# legatus_1_0.net
KiCad netlist of a schematic drawn in EAGLE
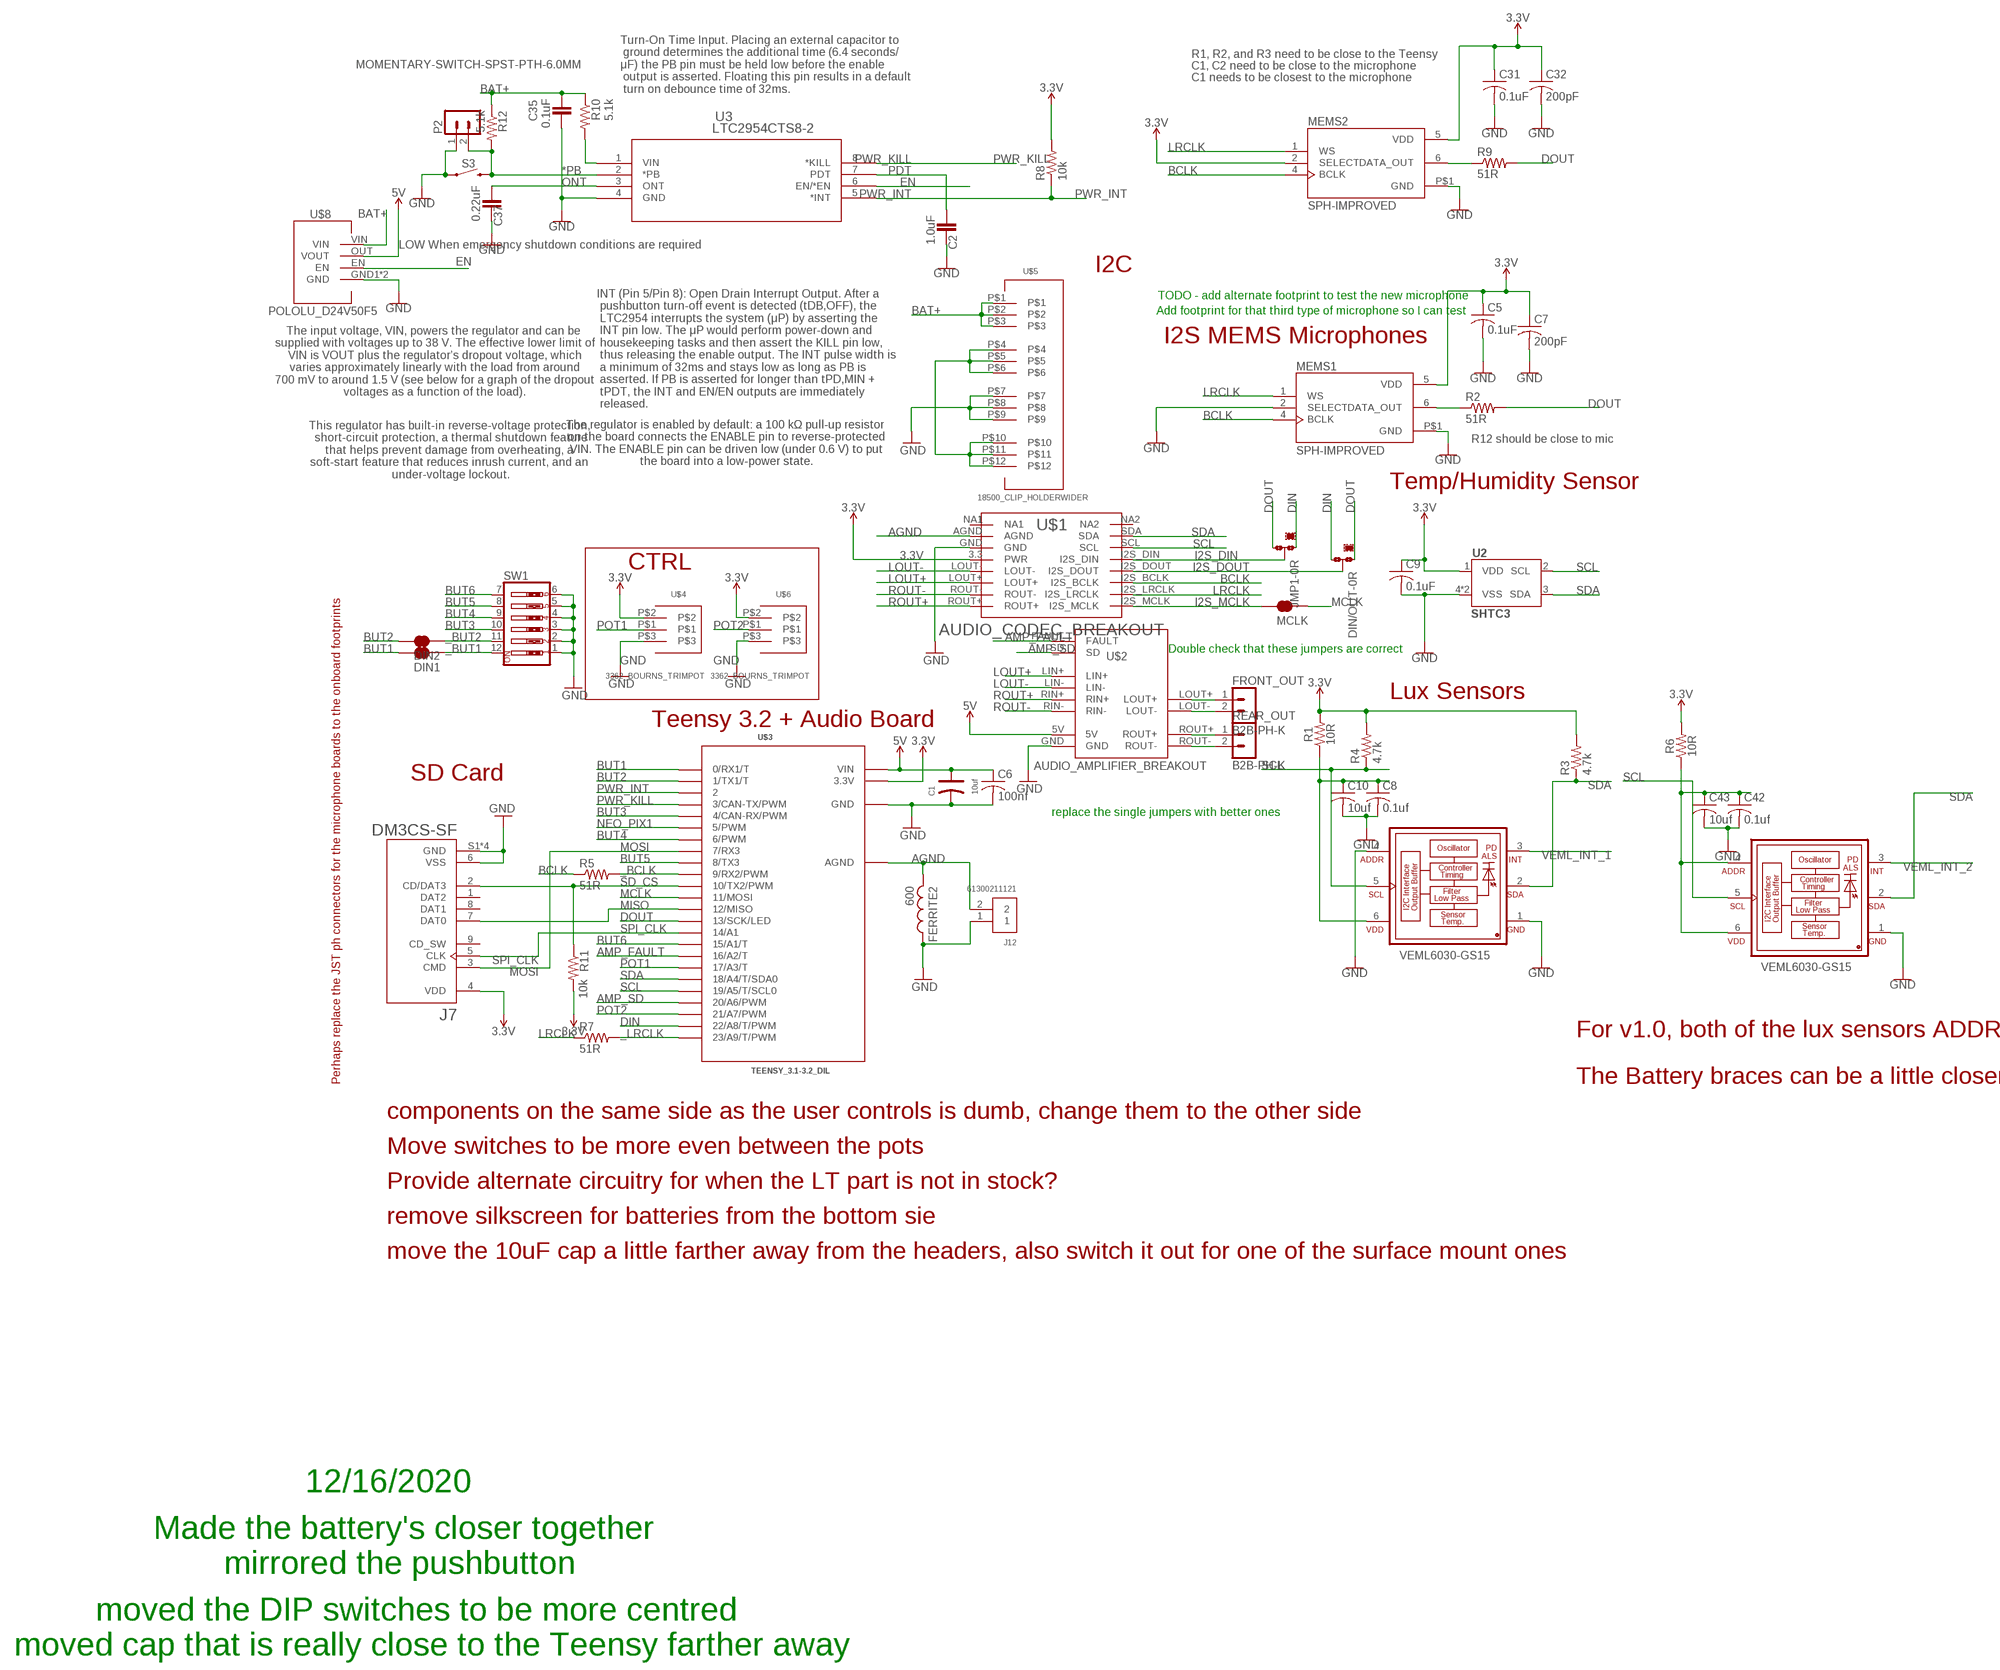
[diagram p0: schematic, sheet 1, part 1 of 2]
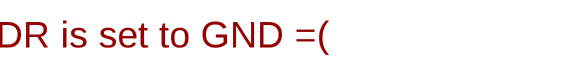
[diagram p1: schematic, sheet 1, part 2 of 2]
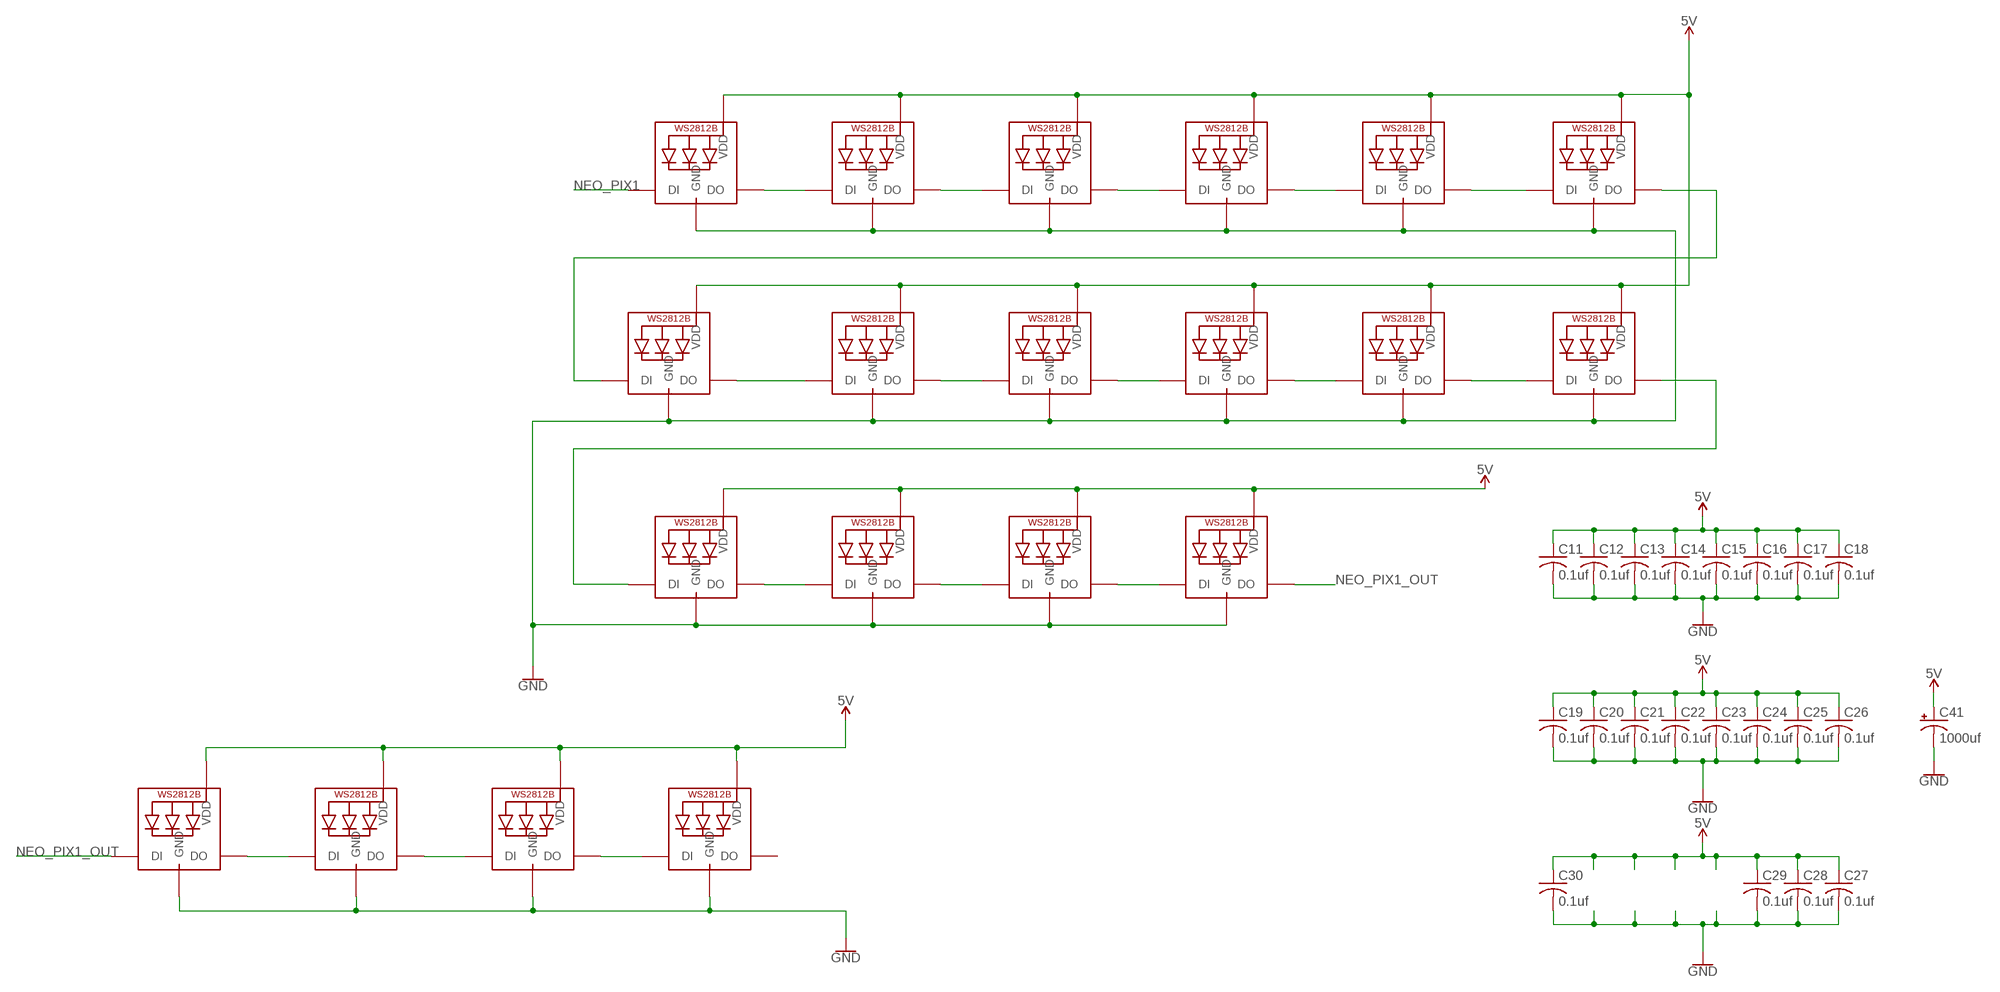
[diagram p2: schematic, sheet 2]

(export (version "E")
  (design (tool "Eeschema 10.0.6"))
  (components
    (comp (ref "C1")
      (value "10uf")
      (footprint "eagle-import:PC-D5.3MM")
      (fields (field (name "MPN") "KS 100uF/16V"))
      (libsource (lib "eagle-import") (part "DIP-ALUMINUM-47UF-16V(D5-H7MM)"))
    )
    (comp (ref "C2")
      (value "1.0uF")
      (footprint "eagle-import:CAPC2012X110")
      (libsource (lib "eagle-import") (part "CCHIP-0805(2012-METRIC)_"))
    )
    (comp (ref "C5")
      (value "0.1uF")
      (footprint "eagle-import:C0805")
      (libsource (lib "eagle-import") (part "rcl_334_C-USC0805"))
    )
    (comp (ref "C6")
      (value "100nf")
      (footprint "eagle-import:C2012")
      (libsource (lib "eagle-import") (part "C-USC2012"))
    )
    (comp (ref "C7")
      (value "200pF")
      (footprint "eagle-import:C0805")
      (libsource (lib "eagle-import") (part "rcl_334_C-USC0805"))
    )
    (comp (ref "C8")
      (value "0.1uf")
      (footprint "eagle-import:C0805")
      (libsource (lib "eagle-import") (part "rcl_334_C-USC0805"))
    )
    (comp (ref "C9")
      (value "0.1uF")
      (footprint "eagle-import:C0805")
      (libsource (lib "eagle-import") (part "rcl_334_C-USC0805"))
    )
    (comp (ref "C10")
      (value "10uf")
      (footprint "eagle-import:C0805")
      (libsource (lib "eagle-import") (part "rcl_334_C-USC0805"))
    )
    (comp (ref "C31")
      (value "0.1uF")
      (footprint "eagle-import:C0805")
      (libsource (lib "eagle-import") (part "rcl_334_C-USC0805"))
    )
    (comp (ref "C32")
      (value "200pF")
      (footprint "eagle-import:C0805")
      (libsource (lib "eagle-import") (part "rcl_334_C-USC0805"))
    )
    (comp (ref "C35")
      (value "0.1uF")
      (footprint "eagle-import:CAPC2012X110")
      (libsource (lib "eagle-import") (part "CCHIP-0805(2012-METRIC)_"))
    )
    (comp (ref "C37")
      (value "0.22uF")
      (footprint "eagle-import:CAPC2012X110")
      (libsource (lib "eagle-import") (part "CCHIP-0805(2012-METRIC)_"))
    )
    (comp (ref "C42")
      (value "0.1uf")
      (footprint "eagle-import:C0805")
      (libsource (lib "eagle-import") (part "rcl_334_C-USC0805"))
    )
    (comp (ref "C43")
      (value "10uf")
      (footprint "eagle-import:C0805")
      (libsource (lib "eagle-import") (part "rcl_334_C-USC0805"))
    )
    (comp (ref "DIN/OUT")
      (value "0R-JUMPB")
      (footprint "eagle-import:B0R-JMP")
      (libsource (lib "eagle-import") (part "0R-JUMPB"))
    )
    (comp (ref "DIN1")
      (value "JUMPER-SMT_2_NC_TRACE_SILK")
      (footprint "eagle-import:SMT-JUMPER_2_NC_TRACE_SILK")
      (libsource (lib "eagle-import") (part "JUMPER-SMT_2_NC_TRACE_SILK"))
    )
    (comp (ref "DIN2")
      (value "JUMPER-SMT_2_NC_TRACE_SILK")
      (footprint "eagle-import:SMT-JUMPER_2_NC_TRACE_SILK")
      (libsource (lib "eagle-import") (part "JUMPER-SMT_2_NC_TRACE_SILK"))
    )
    (comp (ref "FERRITE2")
      (value "600")
      (footprint "eagle-import:RESC0805_N")
      (libsource (lib "eagle-import") (part "INDUCTOR_0805_N"))
    )
    (comp (ref "FRONT_OUT")
      (value "B2B-PH-K")
      (footprint "eagle-import:B2B-PH-K")
      (libsource (lib "eagle-import") (part "B2B-PH-K"))
    )
    (comp (ref "J7")
      (value "DM3CS-SF")
      (footprint "eagle-import:HRS_DM3CS-SF")
      (fields (field (name "MF") "Hirose"))
      (libsource (lib "eagle-import") (part "DM3CS-SF"))
    )
    (comp (ref "J12")
      (value "61300211121")
      (footprint "eagle-import:61300211121")
      (fields
        (field (name "DIGI_KEY_PART_NUMBER") "732-5315-ND")
        (field (name "MANUFACTURER") "Wurth Electronics Inc.")
        (field (name "CREATED_BY") "PCBLayout.com")
      )
      (libsource (lib "eagle-import") (part "61300211121"))
    )
    (comp (ref "JMP1")
      (value "0R-JUMPB")
      (footprint "eagle-import:B0R-JMP")
      (libsource (lib "eagle-import") (part "0R-JUMPB"))
    )
    (comp (ref "MCLK")
      (value "JUMPER-SMT_2_NC_TRACE_SILK")
      (footprint "eagle-import:SMT-JUMPER_2_NC_TRACE_SILK")
      (libsource (lib "eagle-import") (part "JUMPER-SMT_2_NC_TRACE_SILK"))
    )
    (comp (ref "MEMS1")
      (value "SPH-IMPROVED")
      (footprint "eagle-import:MIC_SPH0645LM4H-B_LARGER_RING")
      (libsource (lib "eagle-import") (part "SPH-IMPROVED"))
    )
    (comp (ref "MEMS2")
      (value "SPH-IMPROVED")
      (footprint "eagle-import:MIC_SPH0645LM4H-B_LARGER_RING")
      (libsource (lib "eagle-import") (part "SPH-IMPROVED"))
    )
    (comp (ref "P2")
      (value "B2B-PH-K")
      (footprint "eagle-import:B2B-PH-K")
      (libsource (lib "eagle-import") (part "B2B-PH-K"))
    )
    (comp (ref "R1")
      (value "10R")
      (footprint "eagle-import:R0805")
      (libsource (lib "eagle-import") (part "audio amplifier example_970892_R-US_R0805"))
    )
    (comp (ref "R2")
      (value "51R")
      (footprint "eagle-import:M0805")
      (libsource (lib "eagle-import") (part "adafruit_420_R-US_M0805"))
    )
    (comp (ref "R3")
      (value "4.7k")
      (footprint "eagle-import:M0805")
      (libsource (lib "eagle-import") (part "adafruit_420_R-US_M0805"))
    )
    (comp (ref "R4")
      (value "4.7k")
      (footprint "eagle-import:M0805")
      (libsource (lib "eagle-import") (part "adafruit_420_R-US_M0805"))
    )
    (comp (ref "R5")
      (value "51R")
      (footprint "eagle-import:M0805")
      (libsource (lib "eagle-import") (part "adafruit_420_R-US_M0805"))
    )
    (comp (ref "R6")
      (value "10R")
      (footprint "eagle-import:R0805")
      (libsource (lib "eagle-import") (part "audio amplifier example_970892_R-US_R0805"))
    )
    (comp (ref "R7")
      (value "51R")
      (footprint "eagle-import:M0805")
      (libsource (lib "eagle-import") (part "adafruit_420_R-US_M0805"))
    )
    (comp (ref "R8")
      (value "10k")
      (footprint "eagle-import:R0805")
      (libsource (lib "eagle-import") (part "R-US_R0805"))
    )
    (comp (ref "R9")
      (value "51R")
      (footprint "eagle-import:M0805")
      (libsource (lib "eagle-import") (part "adafruit_420_R-US_M0805"))
    )
    (comp (ref "R10")
      (value "5.1k")
      (footprint "eagle-import:R0805")
      (libsource (lib "eagle-import") (part "R-US_R0805"))
    )
    (comp (ref "R11")
      (value "10k")
      (footprint "eagle-import:M0805")
      (libsource (lib "eagle-import") (part "rcl_R-US_M0805"))
    )
    (comp (ref "R12")
      (value "5.1k")
      (footprint "eagle-import:R0805")
      (libsource (lib "eagle-import") (part "R-US_R0805"))
    )
    (comp (ref "REAR_OUT")
      (value "B2B-PH-K")
      (footprint "eagle-import:B2B-PH-K")
      (libsource (lib "eagle-import") (part "B2B-PH-K"))
    )
    (comp (ref "S3")
      (value "MOMENTARY-SWITCH-SPST-PTH-6.0MM")
      (footprint "eagle-import:TACTILE_SWITCH_PTH_6.0MM")
      (libsource (lib "eagle-import") (part "MOMENTARY-SWITCH-SPST-PTH-6.0MM"))
    )
    (comp (ref "SW1")
      (value "SW_DIP-6")
      (footprint "eagle-import:EDG-06")
      (libsource (lib "eagle-import") (part "SW_DIP-6"))
    )
    (comp (ref "U$1")
      (value "AUDIO_CODEC_BREAKOUT")
      (footprint "eagle-import:HSS_CODEC_BREAKOUT")
      (libsource (lib "eagle-import") (part "AUDIO_CODEC_BREAKOUT"))
    )
    (comp (ref "U$2")
      (value "AUDIO_AMPLIFIER_BREAKOUT")
      (footprint "eagle-import:AUDIO_AMPLIFIER_BREAKOUT")
      (libsource (lib "eagle-import") (part "AUDIO_AMPLIFIER_BREAKOUT"))
    )
    (comp (ref "U$3")
      (value "TEENSY_3.1-3.2_DIL")
      (footprint "eagle-import:TEENSY_3.0-3.2&LC_DIL")
      (libsource (lib "eagle-import") (part "TEENSY_3.1-3.2_DIL"))
    )
    (comp (ref "U$4")
      (value "3362_BOURNS_TRIMPOT")
      (footprint "eagle-import:3362_BOURNS_TRIMPOT")
      (libsource (lib "eagle-import") (part "3362_BOURNS_TRIMPOT"))
    )
    (comp (ref "U$5")
      (value "18500_CLIP_HOLDERWIDER")
      (footprint "eagle-import:3PINBATTERY_CLIP_WIDER")
      (libsource (lib "eagle-import") (part "18500_CLIP_HOLDERWIDER"))
    )
    (comp (ref "U$6")
      (value "3362_BOURNS_TRIMPOT")
      (footprint "eagle-import:3362_BOURNS_TRIMPOT")
      (libsource (lib "eagle-import") (part "3362_BOURNS_TRIMPOT"))
    )
    (comp (ref "U$8")
      (value "POLOLU_D24V50F5")
      (footprint "eagle-import:POLOLU_D24V50F5")
      (libsource (lib "eagle-import") (part "POLOLU_D24V50F5"))
    )
    (comp (ref "U2")
      (value "SHTC3")
      (footprint "eagle-import:SHTC3")
      (libsource (lib "eagle-import") (part "SHTC3"))
    )
    (comp (ref "U3")
      (value "LTC2954CTS8-2")
      (footprint "eagle-import:TSOT-23_TS8")
      (fields (field (name "MF") "Analog Devices / Linear Technology"))
      (libsource (lib "eagle-import") (part "LTC2954CTS8-2"))
    )
    (comp (ref "VMEL1")
      (value "VEML6030-GS15")
      (footprint "eagle-import:VISHAY_VEML6030_2X2X0.87")
      (fields (field (name "MF") "Vishay Semiconductor"))
      (libsource (lib "eagle-import") (part "VEML6030-GS15"))
    )
    (comp (ref "VMEL2")
      (value "VEML6030-GS15")
      (footprint "eagle-import:VISHAY_VEML6030_2X2X0.87")
      (fields (field (name "MF") "Vishay Semiconductor"))
      (libsource (lib "eagle-import") (part "VEML6030-GS15"))
    )
    (comp (ref "C11")
      (value "0.1uf")
      (footprint "eagle-import:C0805")
      (libsource (lib "eagle-import") (part "rcl_334_C-USC0805"))
    )
    (comp (ref "C12")
      (value "0.1uf")
      (footprint "eagle-import:C0805")
      (libsource (lib "eagle-import") (part "rcl_334_C-USC0805"))
    )
    (comp (ref "C13")
      (value "0.1uf")
      (footprint "eagle-import:C0805")
      (libsource (lib "eagle-import") (part "rcl_334_C-USC0805"))
    )
    (comp (ref "C14")
      (value "0.1uf")
      (footprint "eagle-import:C0805")
      (libsource (lib "eagle-import") (part "rcl_334_C-USC0805"))
    )
    (comp (ref "C15")
      (value "0.1uf")
      (footprint "eagle-import:C0805")
      (libsource (lib "eagle-import") (part "rcl_334_C-USC0805"))
    )
    (comp (ref "C16")
      (value "0.1uf")
      (footprint "eagle-import:C0805")
      (libsource (lib "eagle-import") (part "rcl_334_C-USC0805"))
    )
    (comp (ref "C17")
      (value "0.1uf")
      (footprint "eagle-import:C0805")
      (libsource (lib "eagle-import") (part "rcl_334_C-USC0805"))
    )
    (comp (ref "C18")
      (value "0.1uf")
      (footprint "eagle-import:C0805")
      (libsource (lib "eagle-import") (part "rcl_334_C-USC0805"))
    )
    (comp (ref "C19")
      (value "0.1uf")
      (footprint "eagle-import:C0805")
      (libsource (lib "eagle-import") (part "rcl_334_C-USC0805"))
    )
    (comp (ref "C20")
      (value "0.1uf")
      (footprint "eagle-import:C0805")
      (libsource (lib "eagle-import") (part "rcl_334_C-USC0805"))
    )
    (comp (ref "C21")
      (value "0.1uf")
      (footprint "eagle-import:C0805")
      (libsource (lib "eagle-import") (part "rcl_334_C-USC0805"))
    )
    (comp (ref "C22")
      (value "0.1uf")
      (footprint "eagle-import:C0805")
      (libsource (lib "eagle-import") (part "rcl_334_C-USC0805"))
    )
    (comp (ref "C23")
      (value "0.1uf")
      (footprint "eagle-import:C0805")
      (libsource (lib "eagle-import") (part "rcl_334_C-USC0805"))
    )
    (comp (ref "C24")
      (value "0.1uf")
      (footprint "eagle-import:C0805")
      (libsource (lib "eagle-import") (part "rcl_334_C-USC0805"))
    )
    (comp (ref "C25")
      (value "0.1uf")
      (footprint "eagle-import:C0805")
      (libsource (lib "eagle-import") (part "rcl_334_C-USC0805"))
    )
    (comp (ref "C26")
      (value "0.1uf")
      (footprint "eagle-import:C0805")
      (libsource (lib "eagle-import") (part "rcl_334_C-USC0805"))
    )
    (comp (ref "C27")
      (value "0.1uf")
      (footprint "eagle-import:C0805")
      (libsource (lib "eagle-import") (part "rcl_334_C-USC0805"))
    )
    (comp (ref "C28")
      (value "0.1uf")
      (footprint "eagle-import:C0805")
      (libsource (lib "eagle-import") (part "rcl_334_C-USC0805"))
    )
    (comp (ref "C29")
      (value "0.1uf")
      (footprint "eagle-import:C0805")
      (libsource (lib "eagle-import") (part "rcl_334_C-USC0805"))
    )
    (comp (ref "C30")
      (value "0.1uf")
      (footprint "eagle-import:C0805")
      (libsource (lib "eagle-import") (part "rcl_334_C-USC0805"))
    )
    (comp (ref "C41")
      (value "1000uf")
      (footprint "eagle-import:153CLV-1010")
      (libsource (lib "eagle-import") (part "CPOL-US153CLV-1010"))
    )
    (comp (ref "LED1")
      (value "WS2812B_5050N")
      (footprint "eagle-import:WS2812B-NARROW")
      (libsource (lib "eagle-import") (part "WS2812B_5050N"))
    )
    (comp (ref "LED2")
      (value "WS2812B_5050N")
      (footprint "eagle-import:WS2812B-NARROW")
      (libsource (lib "eagle-import") (part "WS2812B_5050N"))
    )
    (comp (ref "LED3")
      (value "WS2812B_5050N")
      (footprint "eagle-import:WS2812B-NARROW")
      (libsource (lib "eagle-import") (part "WS2812B_5050N"))
    )
    (comp (ref "LED4")
      (value "WS2812B_5050N")
      (footprint "eagle-import:WS2812B-NARROW")
      (libsource (lib "eagle-import") (part "WS2812B_5050N"))
    )
    (comp (ref "LED5")
      (value "WS2812B_5050N")
      (footprint "eagle-import:WS2812B-NARROW")
      (libsource (lib "eagle-import") (part "WS2812B_5050N"))
    )
    (comp (ref "LED6")
      (value "WS2812B_5050N")
      (footprint "eagle-import:WS2812B-NARROW")
      (libsource (lib "eagle-import") (part "WS2812B_5050N"))
    )
    (comp (ref "LED7")
      (value "WS2812B_5050N")
      (footprint "eagle-import:WS2812B-NARROW")
      (libsource (lib "eagle-import") (part "WS2812B_5050N"))
    )
    (comp (ref "LED8")
      (value "WS2812B_5050N")
      (footprint "eagle-import:WS2812B-NARROW")
      (libsource (lib "eagle-import") (part "WS2812B_5050N"))
    )
    (comp (ref "LED9")
      (value "WS2812B_5050N")
      (footprint "eagle-import:WS2812B-NARROW")
      (libsource (lib "eagle-import") (part "WS2812B_5050N"))
    )
    (comp (ref "LED10")
      (value "WS2812B_5050N")
      (footprint "eagle-import:WS2812B-NARROW")
      (libsource (lib "eagle-import") (part "WS2812B_5050N"))
    )
    (comp (ref "LED11")
      (value "WS2812B_5050N")
      (footprint "eagle-import:WS2812B-NARROW")
      (libsource (lib "eagle-import") (part "WS2812B_5050N"))
    )
    (comp (ref "LED12")
      (value "WS2812B_5050N")
      (footprint "eagle-import:WS2812B-NARROW")
      (libsource (lib "eagle-import") (part "WS2812B_5050N"))
    )
    (comp (ref "LED13")
      (value "WS2812B_5050N")
      (footprint "eagle-import:WS2812B-NARROW")
      (libsource (lib "eagle-import") (part "WS2812B_5050N"))
    )
    (comp (ref "LED14")
      (value "WS2812B_5050N")
      (footprint "eagle-import:WS2812B-NARROW")
      (libsource (lib "eagle-import") (part "WS2812B_5050N"))
    )
    (comp (ref "LED15")
      (value "WS2812B_5050N")
      (footprint "eagle-import:WS2812B-NARROW")
      (libsource (lib "eagle-import") (part "WS2812B_5050N"))
    )
    (comp (ref "LED16")
      (value "WS2812B_5050N")
      (footprint "eagle-import:WS2812B-NARROW")
      (libsource (lib "eagle-import") (part "WS2812B_5050N"))
    )
    (comp (ref "LED17")
      (value "WS2812B_5050N")
      (footprint "eagle-import:WS2812B-NARROW")
      (libsource (lib "eagle-import") (part "WS2812B_5050N"))
    )
    (comp (ref "LED18")
      (value "WS2812B_5050N")
      (footprint "eagle-import:WS2812B-NARROW")
      (libsource (lib "eagle-import") (part "WS2812B_5050N"))
    )
    (comp (ref "LED19")
      (value "WS2812B_5050N")
      (footprint "eagle-import:WS2812B-NARROW")
      (libsource (lib "eagle-import") (part "WS2812B_5050N"))
    )
    (comp (ref "LED20")
      (value "WS2812B_5050N")
      (footprint "eagle-import:WS2812B-NARROW")
      (libsource (lib "eagle-import") (part "WS2812B_5050N"))
    )
  )
  (nets
    (net (code "1") (name "*PB") (class "Default")
      (node (ref "P2") (pin "2") (pinfunction "2_2") (pintype "passive"))
      (node (ref "R12") (pin "2") (pinfunction "2_2") (pintype "passive"))
      (node (ref "S3") (pin "3") (pinfunction "2_3") (pintype "passive"))
      (node (ref "U3") (pin "2") (pinfunction "*PB_2") (pintype "input"))
    )
    (net (code "2") (name "3.3V") (class "Default")
      (node (ref "C31") (pin "1") (pinfunction "1_1") (pintype "passive"))
      (node (ref "C32") (pin "1") (pinfunction "1_1") (pintype "passive"))
      (node (ref "C5") (pin "1") (pinfunction "1_1") (pintype "passive"))
      (node (ref "C7") (pin "1") (pinfunction "1_1") (pintype "passive"))
      (node (ref "C9") (pin "1") (pinfunction "1_1") (pintype "passive"))
      (node (ref "J7") (pin "4") (pinfunction "VDD_4") (pintype "passive"))
      (node (ref "MEMS1") (pin "5") (pinfunction "VDD_5") (pintype "power_in"))
      (node (ref "MEMS2") (pin "2") (pinfunction "SELECT_2") (pintype "input"))
      (node (ref "MEMS2") (pin "5") (pinfunction "VDD_5") (pintype "power_in"))
      (node (ref "R1") (pin "2") (pinfunction "2_2") (pintype "passive"))
      (node (ref "R11") (pin "2") (pinfunction "2_2") (pintype "passive"))
      (node (ref "R3") (pin "2") (pinfunction "2_2") (pintype "passive"))
      (node (ref "R4") (pin "2") (pinfunction "2_2") (pintype "passive"))
      (node (ref "R6") (pin "2") (pinfunction "2_2") (pintype "passive"))
      (node (ref "R8") (pin "2") (pinfunction "2_2") (pintype "passive"))
      (node (ref "U$1") (pin "3.3") (pinfunction "PWR_3.3") (pintype "bidirectional"))
      (node (ref "U$3") (pin "3.3V") (pinfunction "3.3V_3.3V") (pintype "power_in"))
      (node (ref "U$4") (pin "P$2") (pinfunction "P$2_P$2") (pintype "bidirectional"))
      (node (ref "U$6") (pin "P$2") (pinfunction "P$2_P$2") (pintype "bidirectional"))
      (node (ref "U2") (pin "1") (pinfunction "VDD_1") (pintype "bidirectional"))
    )
    (net (code "3") (name "5V") (class "Default")
      (node (ref "C1") (pin "+") (pinfunction "+_+") (pintype "passive"))
      (node (ref "C11") (pin "1") (pinfunction "1_1") (pintype "passive"))
      (node (ref "C12") (pin "1") (pinfunction "1_1") (pintype "passive"))
      (node (ref "C13") (pin "1") (pinfunction "1_1") (pintype "passive"))
      (node (ref "C14") (pin "1") (pinfunction "1_1") (pintype "passive"))
      (node (ref "C15") (pin "1") (pinfunction "1_1") (pintype "passive"))
      (node (ref "C16") (pin "1") (pinfunction "1_1") (pintype "passive"))
      (node (ref "C17") (pin "1") (pinfunction "1_1") (pintype "passive"))
      (node (ref "C18") (pin "1") (pinfunction "1_1") (pintype "passive"))
      (node (ref "C19") (pin "1") (pinfunction "1_1") (pintype "passive"))
      (node (ref "C20") (pin "1") (pinfunction "1_1") (pintype "passive"))
      (node (ref "C21") (pin "1") (pinfunction "1_1") (pintype "passive"))
      (node (ref "C22") (pin "1") (pinfunction "1_1") (pintype "passive"))
      (node (ref "C23") (pin "1") (pinfunction "1_1") (pintype "passive"))
      (node (ref "C24") (pin "1") (pinfunction "1_1") (pintype "passive"))
      (node (ref "C25") (pin "1") (pinfunction "1_1") (pintype "passive"))
      (node (ref "C26") (pin "1") (pinfunction "1_1") (pintype "passive"))
      (node (ref "C27") (pin "1") (pinfunction "1_1") (pintype "passive"))
      (node (ref "C28") (pin "1") (pinfunction "1_1") (pintype "passive"))
      (node (ref "C29") (pin "1") (pinfunction "1_1") (pintype "passive"))
      (node (ref "C30") (pin "1") (pinfunction "1_1") (pintype "passive"))
      (node (ref "C41") (pin "+") (pinfunction "+_+") (pintype "passive"))
      (node (ref "C6") (pin "1") (pinfunction "1_1") (pintype "passive"))
      (node (ref "LED1") (pin "1-VDD") (pinfunction "VDD_1-VDD") (pintype "power_in"))
      (node (ref "LED10") (pin "1-VDD") (pinfunction "VDD_1-VDD") (pintype "power_in"))
      (node (ref "LED11") (pin "1-VDD") (pinfunction "VDD_1-VDD") (pintype "power_in"))
      (node (ref "LED12") (pin "1-VDD") (pinfunction "VDD_1-VDD") (pintype "power_in"))
      (node (ref "LED13") (pin "1-VDD") (pinfunction "VDD_1-VDD") (pintype "power_in"))
      (node (ref "LED14") (pin "1-VDD") (pinfunction "VDD_1-VDD") (pintype "power_in"))
      (node (ref "LED15") (pin "1-VDD") (pinfunction "VDD_1-VDD") (pintype "power_in"))
      (node (ref "LED16") (pin "1-VDD") (pinfunction "VDD_1-VDD") (pintype "power_in"))
      (node (ref "LED17") (pin "1-VDD") (pinfunction "VDD_1-VDD") (pintype "power_in"))
      (node (ref "LED18") (pin "1-VDD") (pinfunction "VDD_1-VDD") (pintype "power_in"))
      (node (ref "LED19") (pin "1-VDD") (pinfunction "VDD_1-VDD") (pintype "power_in"))
      (node (ref "LED2") (pin "1-VDD") (pinfunction "VDD_1-VDD") (pintype "power_in"))
      (node (ref "LED20") (pin "1-VDD") (pinfunction "VDD_1-VDD") (pintype "power_in"))
      (node (ref "LED3") (pin "1-VDD") (pinfunction "VDD_1-VDD") (pintype "power_in"))
      (node (ref "LED4") (pin "1-VDD") (pinfunction "VDD_1-VDD") (pintype "power_in"))
      (node (ref "LED5") (pin "1-VDD") (pinfunction "VDD_1-VDD") (pintype "power_in"))
      (node (ref "LED6") (pin "1-VDD") (pinfunction "VDD_1-VDD") (pintype "power_in"))
      (node (ref "LED7") (pin "1-VDD") (pinfunction "VDD_1-VDD") (pintype "power_in"))
      (node (ref "LED8") (pin "1-VDD") (pinfunction "VDD_1-VDD") (pintype "power_in"))
      (node (ref "LED9") (pin "1-VDD") (pinfunction "VDD_1-VDD") (pintype "power_in"))
      (node (ref "U$2") (pin "5V") (pinfunction "5V_5V") (pintype "bidirectional"))
      (node (ref "U$3") (pin "VIN") (pinfunction "VIN_VIN") (pintype "power_in"))
      (node (ref "U$8") (pin "OUT") (pinfunction "VOUT_OUT") (pintype "bidirectional"))
    )
    (net (code "4") (name "AGND") (class "Default")
      (node (ref "FERRITE2") (pin "2") (pinfunction "2_2") (pintype "passive"))
      (node (ref "J12") (pin "2") (pinfunction "2_2") (pintype "passive"))
      (node (ref "U$1") (pin "AGND") (pinfunction "AGND_AGND") (pintype "bidirectional"))
      (node (ref "U$3") (pin "AGND") (pinfunction "AGND_AGND") (pintype "power_in"))
    )
    (net (code "5") (name "AMP_FAULT") (class "Default")
      (node (ref "U$2") (pin "FAULT") (pinfunction "FAULT_FAULT") (pintype "bidirectional"))
      (node (ref "U$3") (pin "16/A2") (pinfunction "16/A2/T_16/A2") (pintype "bidirectional"))
    )
    (net (code "6") (name "AMP_SD") (class "Default")
      (node (ref "U$2") (pin "SD") (pinfunction "SD_SD") (pintype "bidirectional"))
      (node (ref "U$3") (pin "20/A6") (pinfunction "20/A6/PWM_20/A6") (pintype "bidirectional"))
    )
    (net (code "7") (name "BAT+") (class "Default")
      (node (ref "C35") (pin "1") (pinfunction "1_1") (pintype "passive"))
      (node (ref "R10") (pin "1") (pinfunction "1_1") (pintype "passive"))
      (node (ref "R12") (pin "1") (pinfunction "1_1") (pintype "passive"))
      (node (ref "U$5") (pin "P$1") (pinfunction "P$1_P$1") (pintype "bidirectional"))
      (node (ref "U$5") (pin "P$2") (pinfunction "P$2_P$2") (pintype "bidirectional"))
      (node (ref "U$5") (pin "P$3") (pinfunction "P$3_P$3") (pintype "bidirectional"))
      (node (ref "U$8") (pin "VIN") (pinfunction "VIN_VIN") (pintype "bidirectional"))
    )
    (net (code "8") (name "BCLK") (class "Default")
      (node (ref "MEMS1") (pin "4") (pinfunction "BCLK_4") (pintype "input"))
      (node (ref "MEMS2") (pin "4") (pinfunction "BCLK_4") (pintype "input"))
      (node (ref "R5") (pin "1") (pinfunction "1_1") (pintype "passive"))
      (node (ref "U$1") (pin "I2S_BCLK") (pinfunction "I2S_BCLK_I2S_BCLK") (pintype "bidirectional"))
    )
    (net (code "9") (name "BUT1") (class "Default")
      (node (ref "DIN1") (pin "1") (pinfunction "1_1") (pintype "passive"))
      (node (ref "U$3") (pin "0") (pinfunction "0/RX1/T_0") (pintype "bidirectional"))
    )
    (net (code "10") (name "BUT2") (class "Default")
      (node (ref "DIN2") (pin "1") (pinfunction "1_1") (pintype "passive"))
      (node (ref "U$3") (pin "1") (pinfunction "1/TX1/T_1") (pintype "bidirectional"))
    )
    (net (code "11") (name "BUT3") (class "Default")
      (node (ref "SW1") (pin "10") (pinfunction "10_10") (pintype "passive"))
      (node (ref "U$3") (pin "4") (pinfunction "4/CAN-RX/PWM_4") (pintype "bidirectional"))
    )
    (net (code "12") (name "BUT4") (class "Default")
      (node (ref "SW1") (pin "9") (pinfunction "9_9") (pintype "passive"))
      (node (ref "U$3") (pin "6") (pinfunction "6/PWM_6") (pintype "bidirectional"))
    )
    (net (code "13") (name "BUT5") (class "Default")
      (node (ref "SW1") (pin "8") (pinfunction "8_8") (pintype "passive"))
      (node (ref "U$3") (pin "8") (pinfunction "8/TX3_8") (pintype "bidirectional"))
    )
    (net (code "14") (name "BUT6") (class "Default")
      (node (ref "SW1") (pin "7") (pinfunction "7_7") (pintype "passive"))
      (node (ref "U$3") (pin "15/A1") (pinfunction "15/A1/T_15/A1") (pintype "bidirectional"))
    )
    (net (code "15") (name "DIN") (class "Default")
      (node (ref "DIN/OUT") (pin "3") (pinfunction "3_3") (pintype "passive"))
      (node (ref "JMP1") (pin "1") (pinfunction "1_1") (pintype "passive"))
      (node (ref "U$3") (pin "22/A8") (pinfunction "22/A8/T/PWM_22/A8") (pintype "bidirectional"))
    )
    (net (code "16") (name "DOUT") (class "Default")
      (node (ref "DIN/OUT") (pin "1") (pinfunction "1_1") (pintype "passive"))
      (node (ref "JMP1") (pin "3") (pinfunction "3_3") (pintype "passive"))
      (node (ref "R2") (pin "2") (pinfunction "2_2") (pintype "passive"))
      (node (ref "R9") (pin "2") (pinfunction "2_2") (pintype "passive"))
      (node (ref "U$3") (pin "13") (pinfunction "13/SCK/LED_13") (pintype "bidirectional"))
    )
    (net (code "17") (name "EN") (class "Default")
      (node (ref "U$8") (pin "EN") (pinfunction "EN_EN") (pintype "bidirectional"))
      (node (ref "U3") (pin "6") (pinfunction "EN/*EN_6") (pintype "output"))
    )
    (net (code "18") (name "GND") (class "Default")
      (node (ref "C1") (pin "-") (pinfunction "-_-") (pintype "passive"))
      (node (ref "C10") (pin "2") (pinfunction "2_2") (pintype "passive"))
      (node (ref "C11") (pin "2") (pinfunction "2_2") (pintype "passive"))
      (node (ref "C12") (pin "2") (pinfunction "2_2") (pintype "passive"))
      (node (ref "C13") (pin "2") (pinfunction "2_2") (pintype "passive"))
      (node (ref "C14") (pin "2") (pinfunction "2_2") (pintype "passive"))
      (node (ref "C15") (pin "2") (pinfunction "2_2") (pintype "passive"))
      (node (ref "C16") (pin "2") (pinfunction "2_2") (pintype "passive"))
      (node (ref "C17") (pin "2") (pinfunction "2_2") (pintype "passive"))
      (node (ref "C18") (pin "2") (pinfunction "2_2") (pintype "passive"))
      (node (ref "C19") (pin "2") (pinfunction "2_2") (pintype "passive"))
      (node (ref "C2") (pin "2") (pinfunction "2_2") (pintype "passive"))
      (node (ref "C20") (pin "2") (pinfunction "2_2") (pintype "passive"))
      (node (ref "C21") (pin "2") (pinfunction "2_2") (pintype "passive"))
      (node (ref "C22") (pin "2") (pinfunction "2_2") (pintype "passive"))
      (node (ref "C23") (pin "2") (pinfunction "2_2") (pintype "passive"))
      (node (ref "C24") (pin "2") (pinfunction "2_2") (pintype "passive"))
      (node (ref "C25") (pin "2") (pinfunction "2_2") (pintype "passive"))
      (node (ref "C26") (pin "2") (pinfunction "2_2") (pintype "passive"))
      (node (ref "C27") (pin "2") (pinfunction "2_2") (pintype "passive"))
      (node (ref "C28") (pin "2") (pinfunction "2_2") (pintype "passive"))
      (node (ref "C29") (pin "2") (pinfunction "2_2") (pintype "passive"))
      (node (ref "C30") (pin "2") (pinfunction "2_2") (pintype "passive"))
      (node (ref "C31") (pin "2") (pinfunction "2_2") (pintype "passive"))
      (node (ref "C32") (pin "2") (pinfunction "2_2") (pintype "passive"))
      (node (ref "C35") (pin "2") (pinfunction "2_2") (pintype "passive"))
      (node (ref "C37") (pin "2") (pinfunction "2_2") (pintype "passive"))
      (node (ref "C41") (pin "-") (pinfunction "-_-") (pintype "passive"))
      (node (ref "C42") (pin "2") (pinfunction "2_2") (pintype "passive"))
      (node (ref "C43") (pin "2") (pinfunction "2_2") (pintype "passive"))
      (node (ref "C5") (pin "2") (pinfunction "2_2") (pintype "passive"))
      (node (ref "C6") (pin "2") (pinfunction "2_2") (pintype "passive"))
      (node (ref "C7") (pin "2") (pinfunction "2_2") (pintype "passive"))
      (node (ref "C8") (pin "2") (pinfunction "2_2") (pintype "passive"))
      (node (ref "C9") (pin "2") (pinfunction "2_2") (pintype "passive"))
      (node (ref "FERRITE2") (pin "1") (pinfunction "1_1") (pintype "passive"))
      (node (ref "J12") (pin "1") (pinfunction "1_1") (pintype "passive"))
      (node (ref "J7") (pin "6") (pinfunction "VSS_6") (pintype "passive"))
      (node (ref "J7") (pin "S1") (pinfunction "GND_S1") (pintype "passive"))
      (node (ref "J7") (pin "S2") (pinfunction "GND_S2") (pintype "passive"))
      (node (ref "J7") (pin "S3") (pinfunction "GND_S3") (pintype "passive"))
      (node (ref "J7") (pin "S5") (pinfunction "GND_S5") (pintype "passive"))
      (node (ref "LED1") (pin "3-GND") (pinfunction "GND_3-GND") (pintype "power_in"))
      (node (ref "LED10") (pin "3-GND") (pinfunction "GND_3-GND") (pintype "power_in"))
      (node (ref "LED11") (pin "3-GND") (pinfunction "GND_3-GND") (pintype "power_in"))
      (node (ref "LED12") (pin "3-GND") (pinfunction "GND_3-GND") (pintype "power_in"))
      (node (ref "LED13") (pin "3-GND") (pinfunction "GND_3-GND") (pintype "power_in"))
      (node (ref "LED14") (pin "3-GND") (pinfunction "GND_3-GND") (pintype "power_in"))
      (node (ref "LED15") (pin "3-GND") (pinfunction "GND_3-GND") (pintype "power_in"))
      (node (ref "LED16") (pin "3-GND") (pinfunction "GND_3-GND") (pintype "power_in"))
      (node (ref "LED17") (pin "3-GND") (pinfunction "GND_3-GND") (pintype "power_in"))
      (node (ref "LED18") (pin "3-GND") (pinfunction "GND_3-GND") (pintype "power_in"))
      (node (ref "LED19") (pin "3-GND") (pinfunction "GND_3-GND") (pintype "power_in"))
      (node (ref "LED2") (pin "3-GND") (pinfunction "GND_3-GND") (pintype "power_in"))
      (node (ref "LED20") (pin "3-GND") (pinfunction "GND_3-GND") (pintype "power_in"))
      (node (ref "LED3") (pin "3-GND") (pinfunction "GND_3-GND") (pintype "power_in"))
      (node (ref "LED4") (pin "3-GND") (pinfunction "GND_3-GND") (pintype "power_in"))
      (node (ref "LED5") (pin "3-GND") (pinfunction "GND_3-GND") (pintype "power_in"))
      (node (ref "LED6") (pin "3-GND") (pinfunction "GND_3-GND") (pintype "power_in"))
      (node (ref "LED7") (pin "3-GND") (pinfunction "GND_3-GND") (pintype "power_in"))
      (node (ref "LED8") (pin "3-GND") (pinfunction "GND_3-GND") (pintype "power_in"))
      (node (ref "LED9") (pin "3-GND") (pinfunction "GND_3-GND") (pintype "power_in"))
      (node (ref "MEMS1") (pin "2") (pinfunction "SELECT_2") (pintype "input"))
      (node (ref "MEMS1") (pin "P$1") (pinfunction "GND_P$1") (pintype "power_in"))
      (node (ref "MEMS2") (pin "P$1") (pinfunction "GND_P$1") (pintype "power_in"))
      (node (ref "P2") (pin "1") (pinfunction "1_1") (pintype "passive"))
      (node (ref "S3") (pin "1") (pinfunction "1_1") (pintype "passive"))
      (node (ref "SW1") (pin "1") (pinfunction "1_1") (pintype "passive"))
      (node (ref "SW1") (pin "2") (pinfunction "2_2") (pintype "passive"))
      (node (ref "SW1") (pin "3") (pinfunction "3_3") (pintype "passive"))
      (node (ref "SW1") (pin "4") (pinfunction "4_4") (pintype "passive"))
      (node (ref "SW1") (pin "5") (pinfunction "5_5") (pintype "passive"))
      (node (ref "SW1") (pin "6") (pinfunction "6_6") (pintype "passive"))
      (node (ref "U$1") (pin "GND") (pinfunction "GND_GND") (pintype "bidirectional"))
      (node (ref "U$2") (pin "GND") (pinfunction "GND_GND") (pintype "bidirectional"))
      (node (ref "U$3") (pin "GND") (pinfunction "GND_GND") (pintype "power_in"))
      (node (ref "U$4") (pin "P$3") (pinfunction "P$3_P$3") (pintype "bidirectional"))
      (node (ref "U$5") (pin "P$7") (pinfunction "P$7_P$7") (pintype "bidirectional"))
      (node (ref "U$5") (pin "P$8") (pinfunction "P$8_P$8") (pintype "bidirectional"))
      (node (ref "U$5") (pin "P$9") (pinfunction "P$9_P$9") (pintype "bidirectional"))
      (node (ref "U$6") (pin "P$3") (pinfunction "P$3_P$3") (pintype "bidirectional"))
      (node (ref "U$8") (pin "GND1") (pinfunction "GND_GND1") (pintype "bidirectional"))
      (node (ref "U$8") (pin "GND2") (pinfunction "GND_GND2") (pintype "bidirectional"))
      (node (ref "U2") (pin "4") (pinfunction "VSS_4") (pintype "bidirectional"))
      (node (ref "U2") (pin "5") (pinfunction "VSS_5") (pintype "bidirectional"))
      (node (ref "U3") (pin "4") (pinfunction "GND_4") (pintype "power_in"))
      (node (ref "VMEL1") (pin "1") (pinfunction "GND_1") (pintype "power_in"))
      (node (ref "VMEL1") (pin "4") (pinfunction "ADDR_4") (pintype "bidirectional"))
      (node (ref "VMEL2") (pin "1") (pinfunction "GND_1") (pintype "power_in"))
    )
    (net (code "19") (name "I2S_DIN") (class "Default")
      (node (ref "JMP1") (pin "2") (pinfunction "2_2") (pintype "passive"))
      (node (ref "U$1") (pin "I2S_DIN") (pinfunction "I2S_DIN_I2S_DIN") (pintype "bidirectional"))
    )
    (net (code "20") (name "I2S_DOUT") (class "Default")
      (node (ref "DIN/OUT") (pin "2") (pinfunction "2_2") (pintype "passive"))
      (node (ref "U$1") (pin "I2S_DOUT") (pinfunction "I2S_DOUT_I2S_DOUT") (pintype "bidirectional"))
    )
    (net (code "21") (name "I2S_MCLK") (class "Default")
      (node (ref "MCLK") (pin "1") (pinfunction "1_1") (pintype "passive"))
      (node (ref "U$1") (pin "I2S_MCLK") (pinfunction "I2S_MCLK_I2S_MCLK") (pintype "bidirectional"))
    )
    (net (code "22") (name "LOUT+") (class "Default")
      (node (ref "U$1") (pin "LOUT+") (pinfunction "LOUT+_LOUT+") (pintype "bidirectional"))
      (node (ref "U$2") (pin "LIN+") (pinfunction "LIN+_LIN+") (pintype "bidirectional"))
    )
    (net (code "23") (name "LOUT-") (class "Default")
      (node (ref "U$1") (pin "LOUT-") (pinfunction "LOUT-_LOUT-") (pintype "bidirectional"))
      (node (ref "U$2") (pin "LIN-") (pinfunction "LIN-_LIN-") (pintype "bidirectional"))
    )
    (net (code "24") (name "LRCLK") (class "Default")
      (node (ref "MEMS1") (pin "1") (pinfunction "WS_1") (pintype "input"))
      (node (ref "MEMS2") (pin "1") (pinfunction "WS_1") (pintype "input"))
      (node (ref "R7") (pin "1") (pinfunction "1_1") (pintype "passive"))
      (node (ref "U$1") (pin "I2S_LRCLK") (pinfunction "I2S_LRCLK_I2S_LRCLK") (pintype "bidirectional"))
    )
    (net (code "25") (name "MCLK") (class "Default")
      (node (ref "MCLK") (pin "2") (pinfunction "2_2") (pintype "passive"))
      (node (ref "U$3") (pin "11") (pinfunction "11/MOSI_11") (pintype "bidirectional"))
    )
    (net (code "26") (name "MISO") (class "Default")
      (node (ref "J7") (pin "7") (pinfunction "DAT0_7") (pintype "passive"))
      (node (ref "U$3") (pin "12") (pinfunction "12/MISO_12") (pintype "bidirectional"))
    )
    (net (code "27") (name "MOSI") (class "Default")
      (node (ref "J7") (pin "3") (pinfunction "CMD_3") (pintype "passive"))
      (node (ref "U$3") (pin "7") (pinfunction "7/RX3_7") (pintype "bidirectional"))
    )
    (net (code "28") (name "NEO_PIX1") (class "Default")
      (node (ref "LED1") (pin "4-DIN") (pinfunction "DI_4-DIN") (pintype "input"))
      (node (ref "U$3") (pin "5") (pinfunction "5/PWM_5") (pintype "bidirectional"))
    )
    (net (code "29") (name "NEO_PIX1_OUT") (class "Default")
      (node (ref "LED16") (pin "2-DOUT") (pinfunction "DO_2-DOUT") (pintype "output"))
      (node (ref "LED17") (pin "4-DIN") (pinfunction "DI_4-DIN") (pintype "input"))
    )
    (net (code "30") (name "Net-(FRONT_OUT-Pad1)") (class "Default")
      (node (ref "FRONT_OUT") (pin "1") (pinfunction "1_1") (pintype "passive"))
      (node (ref "U$2") (pin "LOUT+") (pinfunction "LOUT+_LOUT+") (pintype "bidirectional"))
    )
    (net (code "31") (name "Net-(FRONT_OUT-Pad2)") (class "Default")
      (node (ref "FRONT_OUT") (pin "2") (pinfunction "2_2") (pintype "passive"))
      (node (ref "U$2") (pin "LOUT-") (pinfunction "LOUT-_LOUT-") (pintype "bidirectional"))
    )
    (net (code "32") (name "Net-(LED1-DO)") (class "Default")
      (node (ref "LED1") (pin "2-DOUT") (pinfunction "DO_2-DOUT") (pintype "output"))
      (node (ref "LED2") (pin "4-DIN") (pinfunction "DI_4-DIN") (pintype "input"))
    )
    (net (code "33") (name "Net-(LED2-DO)") (class "Default")
      (node (ref "LED2") (pin "2-DOUT") (pinfunction "DO_2-DOUT") (pintype "output"))
      (node (ref "LED3") (pin "4-DIN") (pinfunction "DI_4-DIN") (pintype "input"))
    )
    (net (code "34") (name "Net-(LED3-DO)") (class "Default")
      (node (ref "LED3") (pin "2-DOUT") (pinfunction "DO_2-DOUT") (pintype "output"))
      (node (ref "LED4") (pin "4-DIN") (pinfunction "DI_4-DIN") (pintype "input"))
    )
    (net (code "35") (name "Net-(LED4-DO)") (class "Default")
      (node (ref "LED4") (pin "2-DOUT") (pinfunction "DO_2-DOUT") (pintype "output"))
      (node (ref "LED5") (pin "4-DIN") (pinfunction "DI_4-DIN") (pintype "input"))
    )
    (net (code "36") (name "Net-(LED5-DO)") (class "Default")
      (node (ref "LED5") (pin "2-DOUT") (pinfunction "DO_2-DOUT") (pintype "output"))
      (node (ref "LED6") (pin "4-DIN") (pinfunction "DI_4-DIN") (pintype "input"))
    )
    (net (code "37") (name "Net-(LED6-DO)") (class "Default")
      (node (ref "LED6") (pin "2-DOUT") (pinfunction "DO_2-DOUT") (pintype "output"))
      (node (ref "LED7") (pin "4-DIN") (pinfunction "DI_4-DIN") (pintype "input"))
    )
    (net (code "38") (name "Net-(LED7-DO)") (class "Default")
      (node (ref "LED7") (pin "2-DOUT") (pinfunction "DO_2-DOUT") (pintype "output"))
      (node (ref "LED8") (pin "4-DIN") (pinfunction "DI_4-DIN") (pintype "input"))
    )
    (net (code "39") (name "Net-(LED8-DO)") (class "Default")
      (node (ref "LED8") (pin "2-DOUT") (pinfunction "DO_2-DOUT") (pintype "output"))
      (node (ref "LED9") (pin "4-DIN") (pinfunction "DI_4-DIN") (pintype "input"))
    )
    (net (code "40") (name "Net-(LED10-DI)") (class "Default")
      (node (ref "LED10") (pin "4-DIN") (pinfunction "DI_4-DIN") (pintype "input"))
      (node (ref "LED9") (pin "2-DOUT") (pinfunction "DO_2-DOUT") (pintype "output"))
    )
    (net (code "41") (name "Net-(LED10-DO)") (class "Default")
      (node (ref "LED10") (pin "2-DOUT") (pinfunction "DO_2-DOUT") (pintype "output"))
      (node (ref "LED11") (pin "4-DIN") (pinfunction "DI_4-DIN") (pintype "input"))
    )
    (net (code "42") (name "Net-(LED11-DO)") (class "Default")
      (node (ref "LED11") (pin "2-DOUT") (pinfunction "DO_2-DOUT") (pintype "output"))
      (node (ref "LED12") (pin "4-DIN") (pinfunction "DI_4-DIN") (pintype "input"))
    )
    (net (code "43") (name "Net-(LED12-DO)") (class "Default")
      (node (ref "LED12") (pin "2-DOUT") (pinfunction "DO_2-DOUT") (pintype "output"))
      (node (ref "LED13") (pin "4-DIN") (pinfunction "DI_4-DIN") (pintype "input"))
    )
    (net (code "44") (name "Net-(LED13-DO)") (class "Default")
      (node (ref "LED13") (pin "2-DOUT") (pinfunction "DO_2-DOUT") (pintype "output"))
      (node (ref "LED14") (pin "4-DIN") (pinfunction "DI_4-DIN") (pintype "input"))
    )
    (net (code "45") (name "Net-(LED14-DO)") (class "Default")
      (node (ref "LED14") (pin "2-DOUT") (pinfunction "DO_2-DOUT") (pintype "output"))
      (node (ref "LED15") (pin "4-DIN") (pinfunction "DI_4-DIN") (pintype "input"))
    )
    (net (code "46") (name "Net-(LED15-DO)") (class "Default")
      (node (ref "LED15") (pin "2-DOUT") (pinfunction "DO_2-DOUT") (pintype "output"))
      (node (ref "LED16") (pin "4-DIN") (pinfunction "DI_4-DIN") (pintype "input"))
    )
    (net (code "47") (name "Net-(LED17-DO)") (class "Default")
      (node (ref "LED17") (pin "2-DOUT") (pinfunction "DO_2-DOUT") (pintype "output"))
      (node (ref "LED18") (pin "4-DIN") (pinfunction "DI_4-DIN") (pintype "input"))
    )
    (net (code "48") (name "Net-(LED18-DO)") (class "Default")
      (node (ref "LED18") (pin "2-DOUT") (pinfunction "DO_2-DOUT") (pintype "output"))
      (node (ref "LED19") (pin "4-DIN") (pinfunction "DI_4-DIN") (pintype "input"))
    )
    (net (code "49") (name "Net-(LED19-DO)") (class "Default")
      (node (ref "LED19") (pin "2-DOUT") (pinfunction "DO_2-DOUT") (pintype "output"))
      (node (ref "LED20") (pin "4-DIN") (pinfunction "DI_4-DIN") (pintype "input"))
    )
    (net (code "50") (name "Net-(MEMS1-DATA_OUT)") (class "Default")
      (node (ref "MEMS1") (pin "6") (pinfunction "DATA_OUT_6") (pintype "output"))
      (node (ref "R2") (pin "1") (pinfunction "1_1") (pintype "passive"))
    )
    (net (code "51") (name "Net-(MEMS2-DATA_OUT)") (class "Default")
      (node (ref "MEMS2") (pin "6") (pinfunction "DATA_OUT_6") (pintype "output"))
      (node (ref "R9") (pin "1") (pinfunction "1_1") (pintype "passive"))
    )
    (net (code "52") (name "Net-(REAR_OUT-Pad1)") (class "Default")
      (node (ref "REAR_OUT") (pin "1") (pinfunction "1_1") (pintype "passive"))
      (node (ref "U$2") (pin "ROUT+") (pinfunction "ROUT+_ROUT+") (pintype "bidirectional"))
    )
    (net (code "53") (name "Net-(REAR_OUT-Pad2)") (class "Default")
      (node (ref "REAR_OUT") (pin "2") (pinfunction "2_2") (pintype "passive"))
      (node (ref "U$2") (pin "ROUT-") (pinfunction "ROUT-_ROUT-") (pintype "bidirectional"))
    )
    (net (code "54") (name "Net-(U$5-PadP$10)") (class "Default")
      (node (ref "U$5") (pin "P$10") (pinfunction "P$10_P$10") (pintype "bidirectional"))
      (node (ref "U$5") (pin "P$11") (pinfunction "P$11_P$11") (pintype "bidirectional"))
      (node (ref "U$5") (pin "P$12") (pinfunction "P$12_P$12") (pintype "bidirectional"))
      (node (ref "U$5") (pin "P$4") (pinfunction "P$4_P$4") (pintype "bidirectional"))
      (node (ref "U$5") (pin "P$5") (pinfunction "P$5_P$5") (pintype "bidirectional"))
      (node (ref "U$5") (pin "P$6") (pinfunction "P$6_P$6") (pintype "bidirectional"))
    )
    (net (code "55") (name "Net-(U3-VIN)") (class "Default")
      (node (ref "R10") (pin "2") (pinfunction "2_2") (pintype "passive"))
      (node (ref "U3") (pin "1") (pinfunction "VIN_1") (pintype "input"))
    )
    (net (code "56") (name "Net-(VMEL1-VDD)") (class "Default")
      (node (ref "C10") (pin "1") (pinfunction "1_1") (pintype "passive"))
      (node (ref "C8") (pin "1") (pinfunction "1_1") (pintype "passive"))
      (node (ref "R1") (pin "1") (pinfunction "1_1") (pintype "passive"))
      (node (ref "VMEL1") (pin "6") (pinfunction "VDD_6") (pintype "power_in"))
    )
    (net (code "57") (name "Net-(VMEL2-ADDR)") (class "Default")
      (node (ref "C42") (pin "1") (pinfunction "1_1") (pintype "passive"))
      (node (ref "C43") (pin "1") (pinfunction "1_1") (pintype "passive"))
      (node (ref "R6") (pin "1") (pinfunction "1_1") (pintype "passive"))
      (node (ref "VMEL2") (pin "4") (pinfunction "ADDR_4") (pintype "bidirectional"))
      (node (ref "VMEL2") (pin "6") (pinfunction "VDD_6") (pintype "power_in"))
    )
    (net (code "58") (name "ONT") (class "Default")
      (node (ref "C37") (pin "1") (pinfunction "1_1") (pintype "passive"))
      (node (ref "U3") (pin "3") (pinfunction "ONT_3") (pintype "input"))
    )
    (net (code "59") (name "PDT") (class "Default")
      (node (ref "C2") (pin "1") (pinfunction "1_1") (pintype "passive"))
      (node (ref "U3") (pin "7") (pinfunction "PDT_7") (pintype "input"))
    )
    (net (code "60") (name "POT1") (class "Default")
      (node (ref "U$3") (pin "17/A3") (pinfunction "17/A3/T_17/A3") (pintype "bidirectional"))
      (node (ref "U$4") (pin "P$1") (pinfunction "P$1_P$1") (pintype "bidirectional"))
    )
    (net (code "61") (name "POT2") (class "Default")
      (node (ref "U$3") (pin "21/A7") (pinfunction "21/A7/PWM_21/A7") (pintype "bidirectional"))
      (node (ref "U$6") (pin "P$1") (pinfunction "P$1_P$1") (pintype "bidirectional"))
    )
    (net (code "62") (name "PWR_INT") (class "Default")
      (node (ref "R8") (pin "1") (pinfunction "1_1") (pintype "passive"))
      (node (ref "U$3") (pin "2") (pinfunction "2_2") (pintype "bidirectional"))
      (node (ref "U3") (pin "5") (pinfunction "*INT_5") (pintype "output"))
    )
    (net (code "63") (name "PWR_KILL") (class "Default")
      (node (ref "U$3") (pin "3") (pinfunction "3/CAN-TX/PWM_3") (pintype "bidirectional"))
      (node (ref "U3") (pin "8") (pinfunction "*KILL_8") (pintype "input"))
    )
    (net (code "64") (name "ROUT+") (class "Default")
      (node (ref "U$1") (pin "ROUT+") (pinfunction "ROUT+_ROUT+") (pintype "bidirectional"))
      (node (ref "U$2") (pin "RIN+") (pinfunction "RIN+_RIN+") (pintype "bidirectional"))
    )
    (net (code "65") (name "ROUT-") (class "Default")
      (node (ref "U$1") (pin "ROUT-") (pinfunction "ROUT-_ROUT-") (pintype "bidirectional"))
      (node (ref "U$2") (pin "RIN-") (pinfunction "RIN-_RIN-") (pintype "bidirectional"))
    )
    (net (code "66") (name "SCL") (class "Default")
      (node (ref "R4") (pin "1") (pinfunction "1_1") (pintype "passive"))
      (node (ref "U$1") (pin "SCL") (pinfunction "SCL_SCL") (pintype "bidirectional"))
      (node (ref "U$3") (pin "19/A5") (pinfunction "19/A5/T/SCL0_19/A5") (pintype "bidirectional"))
      (node (ref "U2") (pin "2") (pinfunction "SCL_2") (pintype "bidirectional"))
      (node (ref "VMEL1") (pin "5") (pinfunction "SCL_5") (pintype "input"))
      (node (ref "VMEL2") (pin "5") (pinfunction "SCL_5") (pintype "input"))
    )
    (net (code "67") (name "SDA") (class "Default")
      (node (ref "R3") (pin "1") (pinfunction "1_1") (pintype "passive"))
      (node (ref "U$1") (pin "SDA") (pinfunction "SDA_SDA") (pintype "bidirectional"))
      (node (ref "U$3") (pin "18/A4") (pinfunction "18/A4/T/SDA0_18/A4") (pintype "bidirectional"))
      (node (ref "U2") (pin "3") (pinfunction "SDA_3") (pintype "bidirectional"))
      (node (ref "VMEL1") (pin "2") (pinfunction "SDA_2") (pintype "bidirectional"))
      (node (ref "VMEL2") (pin "2") (pinfunction "SDA_2") (pintype "bidirectional"))
    )
    (net (code "68") (name "SD_CS") (class "Default")
      (node (ref "J7") (pin "2") (pinfunction "CD/DAT3_2") (pintype "passive"))
      (node (ref "R11") (pin "1") (pinfunction "1_1") (pintype "passive"))
      (node (ref "U$3") (pin "10") (pinfunction "10/TX2/PWM_10") (pintype "bidirectional"))
    )
    (net (code "69") (name "SPI_CLK") (class "Default")
      (node (ref "J7") (pin "5") (pinfunction "CLK_5") (pintype "passive"))
      (node (ref "U$3") (pin "14/A0") (pinfunction "14/A1_14/A0") (pintype "bidirectional"))
    )
    (net (code "70") (name "VEML_INT_1") (class "Default")
      (node (ref "VMEL1") (pin "3") (pinfunction "INT_3") (pintype "output"))
    )
    (net (code "71") (name "VEML_INT_2") (class "Default")
      (node (ref "VMEL2") (pin "3") (pinfunction "INT_3") (pintype "output"))
    )
    (net (code "72") (name "_BCLK") (class "Default")
      (node (ref "R5") (pin "2") (pinfunction "2_2") (pintype "passive"))
      (node (ref "U$3") (pin "9") (pinfunction "9/RX2/PWM_9") (pintype "bidirectional"))
    )
    (net (code "73") (name "_BUT1") (class "Default")
      (node (ref "DIN1") (pin "2") (pinfunction "2_2") (pintype "passive"))
      (node (ref "SW1") (pin "12") (pinfunction "12_12") (pintype "passive"))
    )
    (net (code "74") (name "_BUT2") (class "Default")
      (node (ref "DIN2") (pin "2") (pinfunction "2_2") (pintype "passive"))
      (node (ref "SW1") (pin "11") (pinfunction "11_11") (pintype "passive"))
    )
    (net (code "75") (name "_LRCLK") (class "Default")
      (node (ref "R7") (pin "2") (pinfunction "2_2") (pintype "passive"))
      (node (ref "U$3") (pin "23/A9") (pinfunction "23/A9/T/PWM_23/A9") (pintype "bidirectional"))
    )
    (net (code "76") (name "unconnected-(J7-CD_SW-Pad9)") (class "Default")
      (node (ref "J7") (pin "9") (pinfunction "CD_SW_9") (pintype "passive"))
    )
    (net (code "77") (name "unconnected-(J7-DAT1-Pad8)") (class "Default")
      (node (ref "J7") (pin "8") (pinfunction "DAT1_8") (pintype "passive"))
    )
    (net (code "78") (name "unconnected-(J7-DAT2-Pad1)") (class "Default")
      (node (ref "J7") (pin "1") (pinfunction "DAT2_1") (pintype "passive"))
    )
    (net (code "79") (name "unconnected-(LED20-DO-Pad2-DOUT)") (class "Default")
      (node (ref "LED20") (pin "2-DOUT") (pinfunction "DO_2-DOUT") (pintype "output"))
    )
    (net (code "80") (name "unconnected-(U$1-PadNA1)") (class "Default")
      (node (ref "U$1") (pin "NA1") (pinfunction "NA1_NA1") (pintype "bidirectional"))
    )
    (net (code "81") (name "unconnected-(U$1-PadNA2)") (class "Default")
      (node (ref "U$1") (pin "NA2") (pinfunction "NA2_NA2") (pintype "bidirectional"))
    )
  )
)
